# OSO-MISC-20-015_Vitals_Board_for_Ring.net
KiCad netlist of a schematic drawn in EAGLE
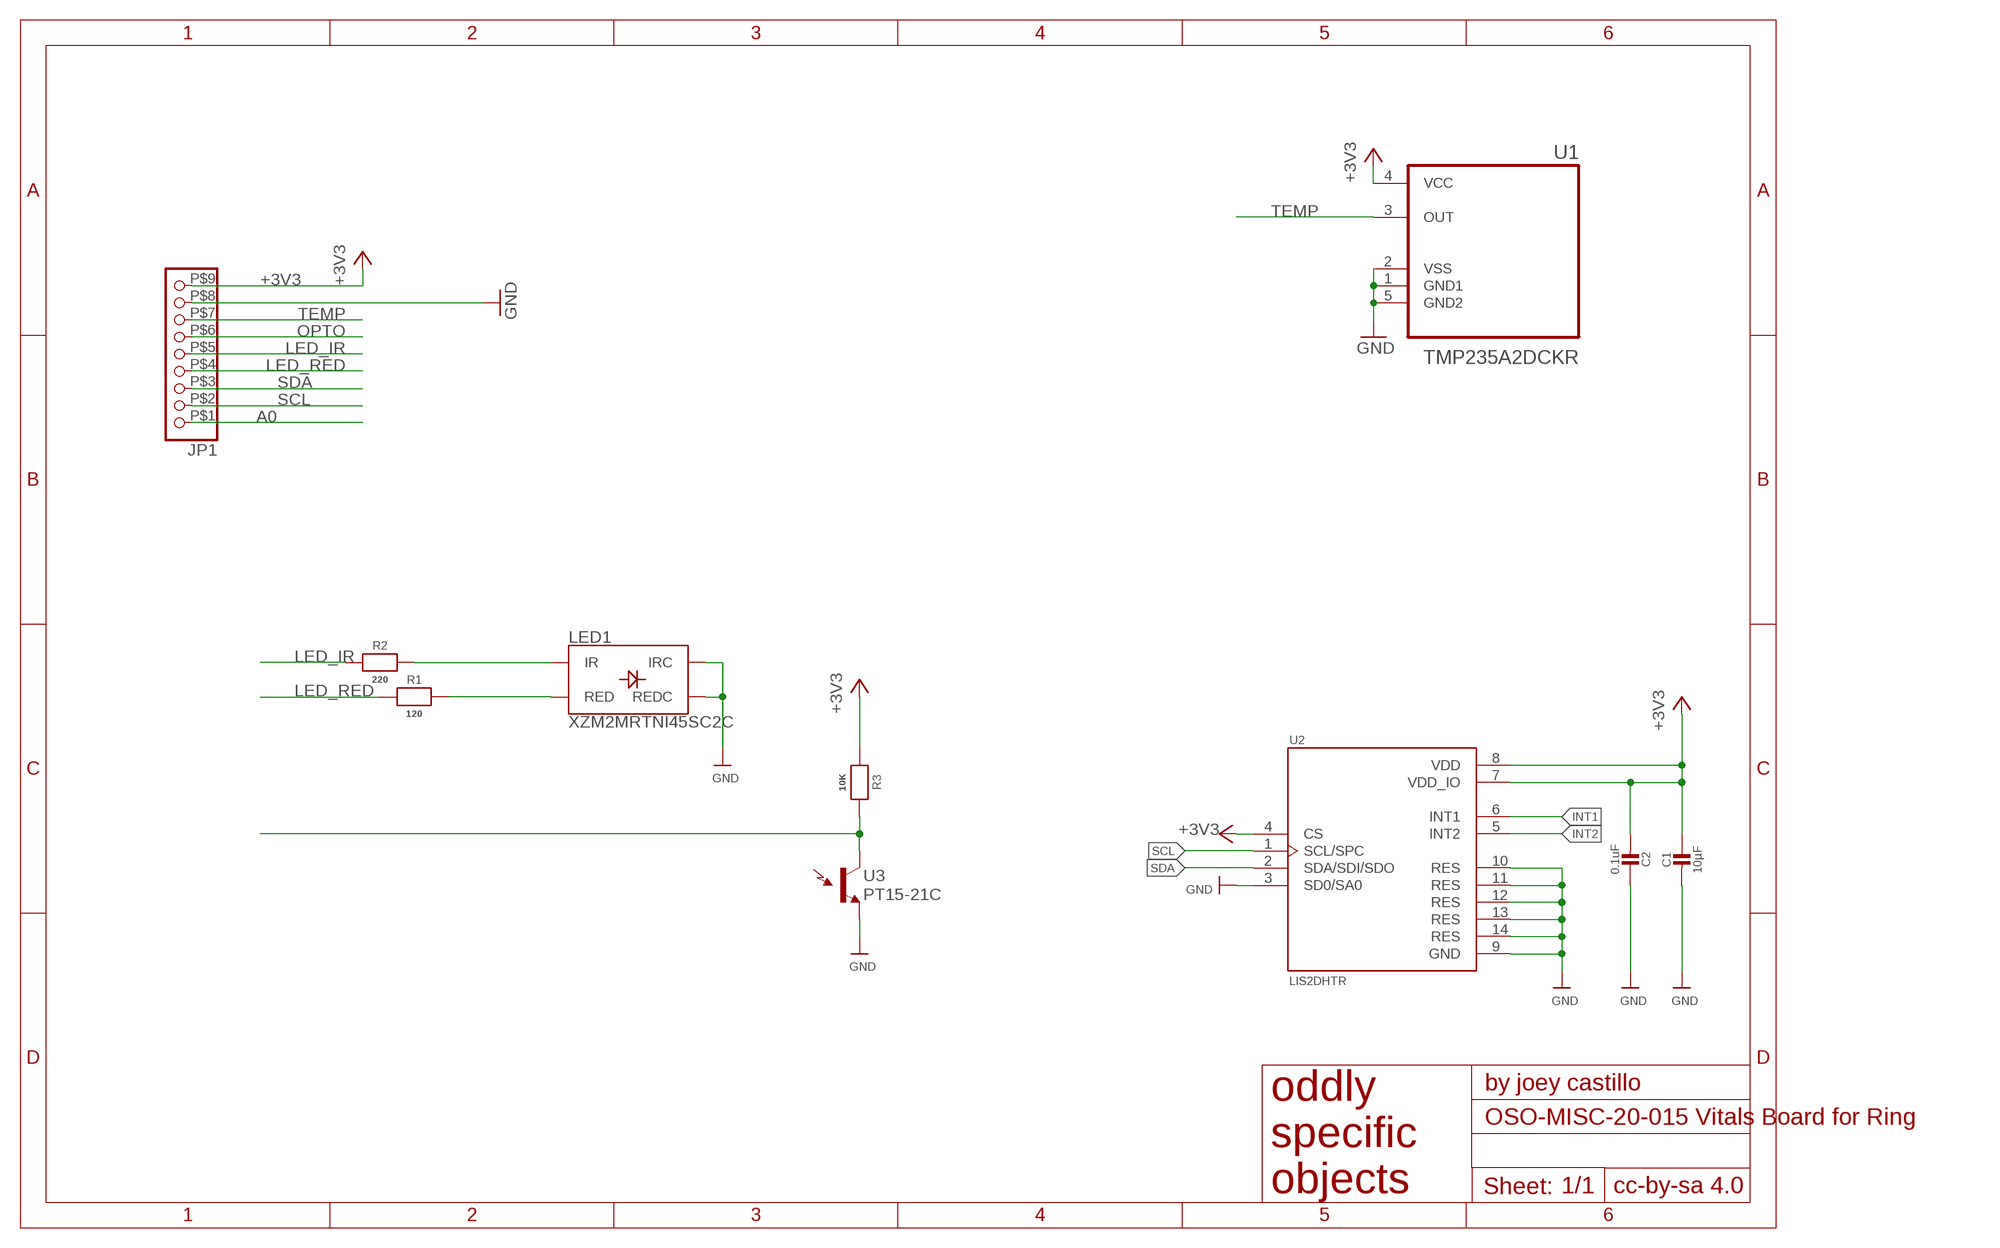
[diagram p0: schematic, sheet 1]

(export (version "E")
  (design (tool "Eeschema 10.0.6"))
  (components
    (comp (ref "C1")
      (value "10µF")
      (footprint "eagle-import:0603-NO")
      (libsource (lib "eagle-import") (part "CAP_CERAMIC0603_NO"))
    )
    (comp (ref "C2")
      (value "0.1uF")
      (footprint "eagle-import:0603-NO")
      (libsource (lib "eagle-import") (part "CAP_CERAMIC0603_NO"))
    )
    (comp (ref "JP1")
      (value "HEADER-1X9BOARD_TO_FLEX")
      (footprint "eagle-import:9PIN_SMT_CONNECTOR")
      (libsource (lib "eagle-import") (part "HEADER-1X9BOARD_TO_FLEX"))
    )
    (comp (ref "LED1")
      (value "XZM2MRTNI45SC2C")
      (footprint "eagle-import:PLCC4SMDLED")
      (libsource (lib "eagle-import") (part "SUNLED_DUAL_RED_IRSMD1"))
    )
    (comp (ref "R1")
      (value "120")
      (footprint "eagle-import:0603-NO")
      (libsource (lib "eagle-import") (part "RESISTOR_0603_NOOUT"))
    )
    (comp (ref "R2")
      (value "220")
      (footprint "eagle-import:0603-NO")
      (libsource (lib "eagle-import") (part "RESISTOR_0603_NOOUT"))
    )
    (comp (ref "R3")
      (value "10K")
      (footprint "eagle-import:0603-NO")
      (libsource (lib "eagle-import") (part "RESISTOR_0603_NOOUT"))
    )
    (comp (ref "U1")
      (value "TMP235A2DCKR")
      (footprint "eagle-import:SOT65P210X110-5N")
      (fields (field (name "DIGI-KEY_PART_NUMBER") "296-50494-1-ND") (field (name "MF") "Texas Instruments"))
      (libsource (lib "eagle-import") (part "TMP235A2DCKR"))
    )
    (comp (ref "U2")
      (value "LIS2DHTR")
      (footprint "eagle-import:PQFN35P200X200X100-14N")
      (fields (field (name "DIGI-KEY_PART_NUMBER") "497-13795-1-ND") (field (name "MF") "STMicroelectronics"))
      (libsource (lib "eagle-import") (part "LIS2DHTR"))
    )
    (comp (ref "U3")
      (value "PT15-21C")
      (footprint "eagle-import:LED-1206")
      (libsource (lib "eagle-import") (part "LIGHT_SENSOR1206"))
    )
  )
  (nets
    (net (code "1") (name "+3V3") (class "Default")
      (node (ref "C1") (pin "1") (pinfunction "1_1") (pintype "passive"))
      (node (ref "C2") (pin "2") (pinfunction "2_2") (pintype "passive"))
      (node (ref "JP1") (pin "P$9") (pinfunction "9_P$9") (pintype "passive"))
      (node (ref "R3") (pin "1") (pinfunction "1_1") (pintype "passive"))
      (node (ref "U1") (pin "4") (pinfunction "VCC_4") (pintype "power_in"))
      (node (ref "U2") (pin "4") (pinfunction "CS_4") (pintype "input"))
      (node (ref "U2") (pin "7") (pinfunction "VDD_IO_7") (pintype "power_in"))
      (node (ref "U2") (pin "8") (pinfunction "VDD_8") (pintype "power_in"))
    )
    (net (code "2") (name "/A0") (class "Default")
      (node (ref "JP1") (pin "P$1") (pinfunction "1_P$1") (pintype "passive"))
    )
    (net (code "3") (name "/LED_IR") (class "Default")
      (node (ref "JP1") (pin "P$5") (pinfunction "5_P$5") (pintype "passive"))
      (node (ref "R2") (pin "1") (pinfunction "1_1") (pintype "passive"))
    )
    (net (code "4") (name "/LED_RED") (class "Default")
      (node (ref "JP1") (pin "P$4") (pinfunction "4_P$4") (pintype "passive"))
      (node (ref "R1") (pin "1") (pinfunction "1_1") (pintype "passive"))
    )
    (net (code "5") (name "/OPTO") (class "Default")
      (node (ref "JP1") (pin "P$6") (pinfunction "6_P$6") (pintype "passive"))
      (node (ref "R3") (pin "2") (pinfunction "2_2") (pintype "passive"))
      (node (ref "U3") (pin "A") (pinfunction "C1_A") (pintype "passive"))
    )
    (net (code "6") (name "/TEMP") (class "Default")
      (node (ref "JP1") (pin "P$7") (pinfunction "7_P$7") (pintype "passive"))
      (node (ref "U1") (pin "3") (pinfunction "OUT_3") (pintype "output"))
    )
    (net (code "7") (name "GND") (class "Default")
      (node (ref "C1") (pin "2") (pinfunction "2_2") (pintype "passive"))
      (node (ref "C2") (pin "1") (pinfunction "1_1") (pintype "passive"))
      (node (ref "JP1") (pin "P$8") (pinfunction "8_P$8") (pintype "passive"))
      (node (ref "LED1") (pin "1") (pinfunction "REDC_1") (pintype "bidirectional"))
      (node (ref "LED1") (pin "3") (pinfunction "IRC_3") (pintype "bidirectional"))
      (node (ref "U1") (pin "1") (pinfunction "GND1_1") (pintype "power_in"))
      (node (ref "U1") (pin "2") (pinfunction "VSS_2") (pintype "power_in"))
      (node (ref "U1") (pin "5") (pinfunction "GND2_5") (pintype "power_in"))
      (node (ref "U2") (pin "10") (pinfunction "RES_10") (pintype "power_in"))
      (node (ref "U2") (pin "11") (pinfunction "RES_11") (pintype "power_in"))
      (node (ref "U2") (pin "12") (pinfunction "RES_12") (pintype "power_in"))
      (node (ref "U2") (pin "13") (pinfunction "RES_13") (pintype "power_in"))
      (node (ref "U2") (pin "14") (pinfunction "RES_14") (pintype "power_in"))
      (node (ref "U2") (pin "3") (pinfunction "SD0/SA0_3") (pintype "output"))
      (node (ref "U2") (pin "9") (pinfunction "GND_9") (pintype "power_in"))
      (node (ref "U3") (pin "C") (pinfunction "E1_C") (pintype "passive"))
    )
    (net (code "8") (name "INT1") (class "Default")
      (node (ref "U2") (pin "6") (pinfunction "INT1_6") (pintype "output"))
    )
    (net (code "9") (name "INT2") (class "Default")
      (node (ref "U2") (pin "5") (pinfunction "INT2_5") (pintype "output"))
    )
    (net (code "10") (name "Net-(LED1-IR)") (class "Default")
      (node (ref "LED1") (pin "4") (pinfunction "IR_4") (pintype "bidirectional"))
      (node (ref "R2") (pin "2") (pinfunction "2_2") (pintype "passive"))
    )
    (net (code "11") (name "Net-(LED1-RED)") (class "Default")
      (node (ref "LED1") (pin "2") (pinfunction "RED_2") (pintype "bidirectional"))
      (node (ref "R1") (pin "2") (pinfunction "2_2") (pintype "passive"))
    )
    (net (code "12") (name "SCL") (class "Default")
      (node (ref "JP1") (pin "P$2") (pinfunction "2_P$2") (pintype "passive"))
      (node (ref "U2") (pin "1") (pinfunction "SCL/SPC_1") (pintype "input"))
    )
    (net (code "13") (name "SDA") (class "Default")
      (node (ref "JP1") (pin "P$3") (pinfunction "3_P$3") (pintype "passive"))
      (node (ref "U2") (pin "2") (pinfunction "SDA/SDI/SDO_2") (pintype "bidirectional"))
    )
  )
)
